# 24V_Buck.net
KiCad netlist of a schematic drawn in Altium Designer
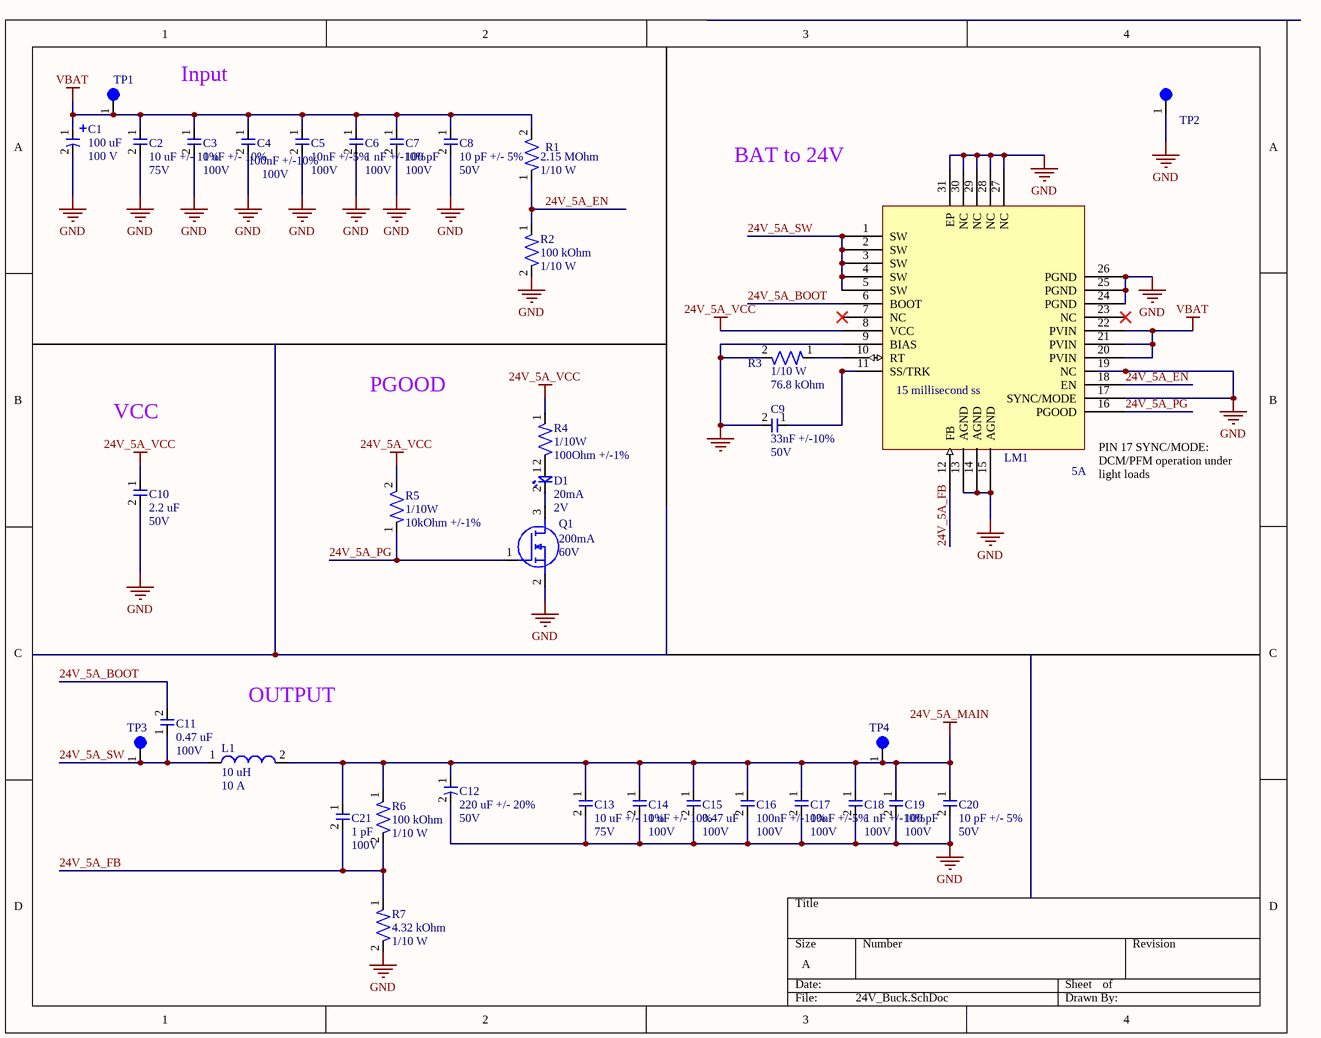
[diagram p0: 24V_Buck.SchDoc]

(export (version "E")
  (design (tool "Eeschema 10.0.6"))
  (components
    (comp (ref "C1")
      (value "100SEV100M12.5X16")
      (footprint "ELEC-100U-0001")
      (description "100 µF 100 V Aluminum Electrolytic Capacitors Radial, Can - SMD 2000 Hrs @ 85°C")
      (fields
        (field (name "MANUFACTURER") "Rubycon")
        (field (name "TOLERANCE") "+/- 20%")
        (field (name "CAPACITANCE") "100 uF")
        (field (name "VOLTAGE") "100 V")
      )
      (libsource (lib "MasterLib") (part "ELEC-100U-0001"))
    )
    (comp (ref "C2")
      (value "C3225X7R1N106K250AC")
      (footprint "CAP-1210")
      (description "10 µF ±10% 75V Ceramic Capacitor X7R 1210 (3225 Metric)")
      (fields (field (name "CAPACITANCE") "10 uF +/- 10%") (field (name "VOLTAGE RATING") "75V"))
      (libsource (lib "MasterLib") (part "CAP-10U-0004"))
    )
    (comp (ref "C3")
      (value "CL31B105KCHNNNE")
      (footprint "CAP-1206 - duplicate")
      (description "1 µF ±10% 100V Ceramic Capacitor X7R 1206 (3216 Metric)")
      (fields (field (name "CAPACITANCE") "1 uF +/- 10%") (field (name "VOLTAGE") "100V"))
      (libsource (lib "MasterLib") (part "CAP-1U-0001"))
    )
    (comp (ref "C4")
      (value "CC0603KRX7R0BB104")
      (footprint "CAP-0603")
      (description "CAP CER 0.1UF 100V X7R 0603")
      (fields
        (field (name "MANUFACTURER") "YAGEO")
        (field (name "CAPACITANCE") "100nF +/-10%")
        (field (name "VOLTAGE RATING") "100V")
      )
      (libsource (lib "MasterLib") (part "CAP-100N-0001"))
    )
    (comp (ref "C5")
      (value "C1608C0G2A103J080AC")
      (footprint "CAP-0603")
      (description "CAP CER 10000PF 100V C0G 0603")
      (fields
        (field (name "MANUFACTURER") "TDK Corporation")
        (field (name "CAPACITANCE") "10nF +/-5%")
        (field (name "VOLTAGE RATING") "100V")
      )
      (libsource (lib "MasterLib") (part "CAP-10N-0002"))
    )
    (comp (ref "C6")
      (value "C0603Y102K1RAC7867")
      (footprint "CAP-0603")
      (description "1000 pF ±10% 100V Ceramic Capacitor X7R 0603 (1608 Metric)")
      (fields (field (name "CAPACITANCE") "1 nF +/-10%") (field (name "VOLTAGE") "100V"))
      (libsource (lib "MasterLib") (part "CAP-1N-0001"))
    )
    (comp (ref "C7")
      (value "0603N101J101CT")
      (footprint "CAP-0603")
      (description "100 pF ±5% 100V Ceramic Capacitor C0G, NP0 0603 (1608 Metric)")
      (fields
        (field (name "TOLERANCE") "+/-5%")
        (field (name "CAPACITANCE") "100 pF")
        (field (name "VOLTAGE") "100V")
      )
      (libsource (lib "MasterLib") (part "CAP-100P-0002"))
    )
    (comp (ref "C8")
      (value "0603N100J500CT")
      (footprint "CAP-0603")
      (description "10 pF ±5% 50V Ceramic Capacitor C0G, NP0 0603 (1608 Metric)")
      (fields
        (field (name "MANUFACTURER") "Walshin Technology Corporation")
        (field (name "CAPACITANCE") "10 pF +/- 5%")
        (field (name "VOLTAGE RATING") "50V")
      )
      (libsource (lib "MasterLib") (part "CAP-10P-0001"))
    )
    (comp (ref "C9")
      (value "CC0603KRX7R9BB333")
      (footprint "CAP-0603")
      (description "0.033 µF ±10% 50V Ceramic Capacitor X7R 0603 (1608 Metric)")
      (fields
        (field (name "MANUFACTURER") "YAGEO")
        (field (name "CAPACITANCE") "33nF +/-10%")
        (field (name "VOLTAGE RATING") "50V")
      )
      (libsource (lib "MasterLib") (part "CAP-33N-0001"))
    )
    (comp (ref "C10")
      (value "UMK107BBJ225KA-T")
      (footprint "CAP-0603")
      (description "2.2 µF ±10% 50V Ceramic Capacitor X5R 0603 (1608 Metric)")
      (fields (field (name "CAPACITANCE") "2.2 uF") (field (name "OLTAGE") "50V"))
      (libsource (lib "MasterLib") (part "CAP-2.2U-0001"))
    )
    (comp (ref "C11")
      (value "KAM21KR72A474KL")
      (footprint "CAP-0805")
      (description "0.47 µF ±10% 100V Ceramic Capacitor X7R 0805 (2012 Metric)")
      (fields
        (field (name "TOLERANCE") "+/- 10%")
        (field (name "CAPACITANCE") "0.47 uF")
        (field (name "VOLTAGE") "100V")
      )
      (libsource (lib "MasterLib") (part "CAP-0.47U-0001"))
    )
    (comp (ref "C12")
      (value "50TZV220M10X10.5")
      (footprint "ELEC-220U-0003")
      (description "220 µF 50 V Aluminum Electrolytic Capacitors Radial, Can - SMD 2000 Hrs @ 105°C")
      (fields (field (name "CAPACITANCE") "220 uF +/- 20%") (field (name "VOLTAGE RATING") "50V"))
      (libsource (lib "MasterLib") (part "ELEC-220U-0003"))
    )
    (comp (ref "C13")
      (value "C3225X7R1N106K250AC")
      (footprint "CAP-1210")
      (description "10 µF ±10% 75V Ceramic Capacitor X7R 1210 (3225 Metric)")
      (fields (field (name "CAPACITANCE") "10 uF +/- 10%") (field (name "VOLTAGE RATING") "75V"))
      (libsource (lib "MasterLib") (part "CAP-10U-0004"))
    )
    (comp (ref "C14")
      (value "CL31B105KCHNNNE")
      (footprint "CAP-1206 - duplicate")
      (description "1 µF ±10% 100V Ceramic Capacitor X7R 1206 (3216 Metric)")
      (fields (field (name "CAPACITANCE") "1 uF +/- 10%") (field (name "VOLTAGE") "100V"))
      (libsource (lib "MasterLib") (part "CAP-1U-0001"))
    )
    (comp (ref "C15")
      (value "KAM21KR72A474KL")
      (footprint "CAP-0805")
      (description "0.47 µF ±10% 100V Ceramic Capacitor X7R 0805 (2012 Metric)")
      (fields
        (field (name "TOLERANCE") "+/- 10%")
        (field (name "CAPACITANCE") "0.47 uF")
        (field (name "VOLTAGE") "100V")
      )
      (libsource (lib "MasterLib") (part "CAP-0.47U-0001"))
    )
    (comp (ref "C16")
      (value "CC0603KRX7R0BB104")
      (footprint "CAP-0603")
      (description "CAP CER 0.1UF 100V X7R 0603")
      (fields
        (field (name "MANUFACTURER") "YAGEO")
        (field (name "CAPACITANCE") "100nF +/-10%")
        (field (name "VOLTAGE RATING") "100V")
      )
      (libsource (lib "MasterLib") (part "CAP-100N-0001"))
    )
    (comp (ref "C17")
      (value "C1608C0G2A103J080AC")
      (footprint "CAP-0603")
      (description "CAP CER 10000PF 100V C0G 0603")
      (fields
        (field (name "MANUFACTURER") "TDK Corporation")
        (field (name "CAPACITANCE") "10nF +/-5%")
        (field (name "VOLTAGE RATING") "100V")
      )
      (libsource (lib "MasterLib") (part "CAP-10N-0002"))
    )
    (comp (ref "C18")
      (value "C0603Y102K1RAC7867")
      (footprint "CAP-0603")
      (description "1000 pF ±10% 100V Ceramic Capacitor X7R 0603 (1608 Metric)")
      (fields (field (name "CAPACITANCE") "1 nF +/-10%") (field (name "VOLTAGE") "100V"))
      (libsource (lib "MasterLib") (part "CAP-1N-0001"))
    )
    (comp (ref "C19")
      (value "0603N101J101CT")
      (footprint "CAP-0603")
      (description "100 pF ±5% 100V Ceramic Capacitor C0G, NP0 0603 (1608 Metric)")
      (fields
        (field (name "TOLERANCE") "+/-5%")
        (field (name "CAPACITANCE") "100 pF")
        (field (name "VOLTAGE") "100V")
      )
      (libsource (lib "MasterLib") (part "CAP-100P-0002"))
    )
    (comp (ref "C20")
      (value "0603N100J500CT")
      (footprint "CAP-0603")
      (description "10 pF ±5% 50V Ceramic Capacitor C0G, NP0 0603 (1608 Metric)")
      (fields
        (field (name "MANUFACTURER") "Walshin Technology Corporation")
        (field (name "CAPACITANCE") "10 pF +/- 5%")
        (field (name "VOLTAGE RATING") "50V")
      )
      (libsource (lib "MasterLib") (part "CAP-10P-0001"))
    )
    (comp (ref "C21")
      (value "885012006087")
      (footprint "CAP-0603")
      (description "1 pF ±0.25pF 100V Ceramic Capacitor C0G, NP0 0603 (1608 Metric)")
      (fields
        (field (name "TOLERANCE") "+/- 0.25 pF")
        (field (name "CAPACITANCE") "1 pF")
        (field (name "VOLTAGE") "100V")
      )
      (libsource (lib "MasterLib") (part "CAP-1P-0001"))
    )
    (comp (ref "D1")
      (value "150060AS75000")
      (footprint "LED-0603")
      (description "CAP CER 0.1UF 100V X7R 0603")
      (fields
        (field (name "MANUFACTURER") "Wurth Electronik")
        (field (name "CURRENT RATING") "20mA")
        (field (name "VF") "2V")
      )
      (libsource (lib "MasterLib") (part "LED_Amber_0001"))
    )
    (comp (ref "L1")
      (value "SRP1270-100M")
      (footprint "PWRIND-10U-0002")
      (description "10 µH Shielded Drum Core, Wirewound Inductor 10 A 16.8mOhm Max Nonstandard")
      (fields
        (field (name "TOLERANCE") "+/- 20%")
        (field (name "INDUCTANCE") "10 uH")
        (field (name "DCI") "10 A")
      )
      (libsource (lib "MasterLib") (part "PWRIND-10U-0002"))
    )
    (comp (ref "LM1")
      (value "LM76005RNPR")
      (footprint "IC-30-WQFN(6x4)")
      (description "Buck Switching Regulator IC Positive Adjustable 1V 1 Output 5A 30-WFQFN Exposed Pad")
      (fields (field (name "MANUFACTURER") "Texas Instruments") (field (name "CURRENT") "5A"))
      (libsource (lib "MasterLib") (part "IC-BUCK-0006"))
    )
    (comp (ref "Q1")
      (value "T2N7002AK,LM")
      (footprint "NMOS-SOT23-3")
      (description "MOSFET N-CH 60V 200MA SOT23")
      (fields
        (field (name "MANUFACTURER") "Toshiba")
        (field (name "ID-CONTINUOUS") "200mA")
        (field (name "VDS-MAX") "60V")
      )
      (libsource (lib "MasterLib") (part "NMOS-200MA-0001"))
    )
    (comp (ref "R1")
      (value "RC0603FR-072M15L")
      (footprint "RES-0603")
      (description "2.15 MOhms ±1% 0.1W, 1/10W Chip Resistor 0603 (1608 Metric) Moisture Resistant Thick Film")
      (fields
        (field (name "TOLERANCE") "+/-1%")
        (field (name "RESISTANCE") "2.15 MOhm")
        (field (name "POWER") "1/10 W")
      )
      (libsource (lib "MasterLib") (part "RES-2.15M-0001"))
    )
    (comp (ref "R2")
      (value "RC0603FR-07100KL")
      (footprint "RES-0603")
      (description "100 kOhms ±1% 0.1W, 1/10W Chip Resistor 0603 (1608 Metric) Moisture Resistant Thick Film")
      (fields
        (field (name "TOLERANCE") "+/- 1%")
        (field (name "RESISTANCE") "100 kOhm")
        (field (name "POWER") "1/10 W")
      )
      (libsource (lib "MasterLib") (part "RES-100K-0003"))
    )
    (comp (ref "R3")
      (value "RC0603FR-0776K8L")
      (footprint "RES-0603")
      (description "76.8 kOhms ±1% 0.1W, 1/10W Chip Resistor 0603 (1608 Metric) Moisture Resistant Thick Film")
      (fields
        (field (name "MANUFACTURER") "Yageo")
        (field (name "TOLERANCE") "+/- 1%")
        (field (name "POWER") "1/10 W")
        (field (name "RESISTANCE") "76.8 kOhm")
      )
      (libsource (lib "MasterLib") (part "RES-76.8K-0001"))
    )
    (comp (ref "R4")
      (value "AC0603FR-10100RL")
      (footprint "RES-0603")
      (description "100 Ohms ±1% 0.1W, 1/10W Chip Resistor 0603 (1608 Metric) Automotive AEC-Q200 Thick Film")
      (fields
        (field (name "MANUFACTURER") "YAGEO")
        (field (name "POWER RATING") "1/10W")
        (field (name "RESISTANCE") "100Ohm +/-1%")
      )
      (libsource (lib "MasterLib") (part "RES-100-0002"))
    )
    (comp (ref "R5")
      (value "RC0603FR-0710KP")
      (footprint "RES-0603")
      (description "RES SMD 10K OHM 1% 1/10W 0603")
      (fields
        (field (name "MANUFACTURER") "YAGEO")
        (field (name "POWER RATING") "1/10W")
        (field (name "RESISTANCE") "10kOhm +/-1%")
      )
      (libsource (lib "MasterLib") (part "RES-10K-0002"))
    )
    (comp (ref "R6")
      (value "RC0603FR-07100KL")
      (footprint "RES-0603")
      (description "100 kOhms ±1% 0.1W, 1/10W Chip Resistor 0603 (1608 Metric) Moisture Resistant Thick Film")
      (fields
        (field (name "TOLERANCE") "+/- 1%")
        (field (name "RESISTANCE") "100 kOhm")
        (field (name "POWER") "1/10 W")
      )
      (libsource (lib "MasterLib") (part "RES-100K-0003"))
    )
    (comp (ref "R7")
      (value "RC0603FR-074K32L")
      (footprint "RES-0603")
      (description "4.32 kOhms ±1% 0.1W, 1/10W Chip Resistor 0603 (1608 Metric) Moisture Resistant Thick Film")
      (fields
        (field (name "TOLERANCE") "+/-1%")
        (field (name "RESISTANCE") "4.32 kOhm")
        (field (name "POWER") "1/10 W")
      )
      (libsource (lib "MasterLib") (part "RES-4.32K-0001"))
    )
    (comp (ref "TP1")
      (value "5003")
      (footprint "TEST-POINT-0001")
      (description "Oranange PC Test Point, Miniature Phoisphor Bronze Silver Plating Through Hole Mounting Type")
      (libsource (lib "MasterLib") (part "TEST-POINT-0001"))
    )
    (comp (ref "TP2")
      (value "5003")
      (footprint "TEST-POINT-0001")
      (description "Oranange PC Test Point, Miniature Phoisphor Bronze Silver Plating Through Hole Mounting Type")
      (libsource (lib "MasterLib") (part "TEST-POINT-0001"))
    )
    (comp (ref "TP3")
      (value "5003")
      (footprint "TEST-POINT-0001")
      (description "Oranange PC Test Point, Miniature Phoisphor Bronze Silver Plating Through Hole Mounting Type")
      (libsource (lib "MasterLib") (part "TEST-POINT-0001"))
    )
    (comp (ref "TP4")
      (value "5003")
      (footprint "TEST-POINT-0001")
      (description "Oranange PC Test Point, Miniature Phoisphor Bronze Silver Plating Through Hole Mounting Type")
      (libsource (lib "MasterLib") (part "TEST-POINT-0001"))
    )
  )
  (nets
    (net (code "1") (name "/24V_5A_BOOT") (class "Default")
      (node (ref "C11") (pin "2") (pinfunction "2_2") (pintype "passive"))
      (node (ref "LM1") (pin "6") (pinfunction "BOOT_6") (pintype "power_in"))
    )
    (net (code "2") (name "/24V_5A_EN") (class "Default")
      (node (ref "LM1") (pin "18") (pinfunction "EN_18") (pintype "power_in"))
      (node (ref "R1") (pin "1") (pinfunction "1_1") (pintype "passive"))
      (node (ref "R2") (pin "1") (pinfunction "1_1") (pintype "passive"))
    )
    (net (code "3") (name "/24V_5A_FB") (class "Default")
      (node (ref "C21") (pin "2") (pinfunction "2_2") (pintype "passive"))
      (node (ref "LM1") (pin "12") (pinfunction "FB_12") (pintype "input"))
      (node (ref "R6") (pin "2") (pinfunction "2_2") (pintype "passive"))
      (node (ref "R7") (pin "1") (pinfunction "1_1") (pintype "passive"))
    )
    (net (code "4") (name "/24V_5A_PG") (class "Default")
      (node (ref "LM1") (pin "16") (pinfunction "PGOOD_16") (pintype "power_in"))
      (node (ref "Q1") (pin "1") (pinfunction "G_1") (pintype "passive"))
      (node (ref "R5") (pin "1") (pinfunction "1_1") (pintype "passive"))
    )
    (net (code "5") (name "/24V_5A_SW") (class "Default")
      (node (ref "C11") (pin "1") (pinfunction "1_1") (pintype "passive"))
      (node (ref "L1") (pin "1") (pinfunction "1_1") (pintype "passive"))
      (node (ref "LM1") (pin "1") (pinfunction "SW_1") (pintype "power_in"))
      (node (ref "LM1") (pin "2") (pinfunction "SW_2") (pintype "power_in"))
      (node (ref "LM1") (pin "3") (pinfunction "SW_3") (pintype "power_in"))
      (node (ref "LM1") (pin "4") (pinfunction "SW_4") (pintype "power_in"))
      (node (ref "LM1") (pin "5") (pinfunction "SW_5") (pintype "power_in"))
      (node (ref "TP3") (pin "1") (pinfunction "0_1") (pintype "passive"))
    )
    (net (code "6") (name "24V_5A_MAIN") (class "Default")
      (node (ref "C12") (pin "1") (pinfunction "1_1") (pintype "passive"))
      (node (ref "C13") (pin "1") (pinfunction "1_1") (pintype "passive"))
      (node (ref "C14") (pin "1") (pinfunction "1_1") (pintype "passive"))
      (node (ref "C15") (pin "1") (pinfunction "1_1") (pintype "passive"))
      (node (ref "C16") (pin "1") (pinfunction "1_1") (pintype "passive"))
      (node (ref "C17") (pin "1") (pinfunction "1_1") (pintype "passive"))
      (node (ref "C18") (pin "1") (pinfunction "1_1") (pintype "passive"))
      (node (ref "C19") (pin "1") (pinfunction "1_1") (pintype "passive"))
      (node (ref "C20") (pin "1") (pinfunction "1_1") (pintype "passive"))
      (node (ref "C21") (pin "1") (pinfunction "1_1") (pintype "passive"))
      (node (ref "L1") (pin "2") (pinfunction "2_2") (pintype "passive"))
      (node (ref "R6") (pin "1") (pinfunction "1_1") (pintype "passive"))
      (node (ref "TP4") (pin "1") (pinfunction "0_1") (pintype "passive"))
    )
    (net (code "7") (name "24V_5A_VCC") (class "Default")
      (node (ref "C10") (pin "1") (pinfunction "1_1") (pintype "passive"))
      (node (ref "LM1") (pin "8") (pinfunction "VCC_8") (pintype "power_in"))
      (node (ref "R4") (pin "1") (pinfunction "1_1") (pintype "passive"))
      (node (ref "R5") (pin "2") (pinfunction "2_2") (pintype "passive"))
    )
    (net (code "8") (name "<NO NET>") (class "Default")
      (node (ref "C9") (pin "2") (pinfunction "2_2") (pintype "passive"))
      (node (ref "LM1") (pin "9") (pinfunction "BIAS_9") (pintype "power_in"))
      (node (ref "R3") (pin "2") (pinfunction "2_2") (pintype "passive"))
    )
    (net (code "9") (name "GND") (class "Default")
      (node (ref "C1") (pin "2") (pinfunction "2_2") (pintype "passive"))
      (node (ref "C10") (pin "2") (pinfunction "2_2") (pintype "passive"))
      (node (ref "C12") (pin "2") (pinfunction "2_2") (pintype "passive"))
      (node (ref "C13") (pin "2") (pinfunction "2_2") (pintype "passive"))
      (node (ref "C14") (pin "2") (pinfunction "2_2") (pintype "passive"))
      (node (ref "C15") (pin "2") (pinfunction "2_2") (pintype "passive"))
      (node (ref "C16") (pin "2") (pinfunction "2_2") (pintype "passive"))
      (node (ref "C17") (pin "2") (pinfunction "2_2") (pintype "passive"))
      (node (ref "C18") (pin "2") (pinfunction "2_2") (pintype "passive"))
      (node (ref "C19") (pin "2") (pinfunction "2_2") (pintype "passive"))
      (node (ref "C2") (pin "2") (pinfunction "2_2") (pintype "passive"))
      (node (ref "C20") (pin "2") (pinfunction "2_2") (pintype "passive"))
      (node (ref "C3") (pin "2") (pinfunction "2_2") (pintype "passive"))
      (node (ref "C4") (pin "2") (pinfunction "2_2") (pintype "passive"))
      (node (ref "C5") (pin "2") (pinfunction "2_2") (pintype "passive"))
      (node (ref "C6") (pin "2") (pinfunction "2_2") (pintype "passive"))
      (node (ref "C7") (pin "2") (pinfunction "2_2") (pintype "passive"))
      (node (ref "C8") (pin "2") (pinfunction "2_2") (pintype "passive"))
      (node (ref "LM1") (pin "13") (pinfunction "AGND_13") (pintype "power_in"))
      (node (ref "LM1") (pin "14") (pinfunction "AGND_14") (pintype "power_in"))
      (node (ref "LM1") (pin "15") (pinfunction "AGND_15") (pintype "power_in"))
      (node (ref "LM1") (pin "17") (pinfunction "SYNC/MODE_17") (pintype "power_in"))
      (node (ref "LM1") (pin "19") (pinfunction "NC_19") (pintype "power_in"))
      (node (ref "LM1") (pin "24") (pinfunction "PGND_24") (pintype "power_in"))
      (node (ref "LM1") (pin "25") (pinfunction "PGND_25") (pintype "power_in"))
      (node (ref "LM1") (pin "26") (pinfunction "PGND_26") (pintype "power_in"))
      (node (ref "LM1") (pin "27") (pinfunction "NC_27") (pintype "power_in"))
      (node (ref "LM1") (pin "28") (pinfunction "NC_28") (pintype "power_in"))
      (node (ref "LM1") (pin "29") (pinfunction "NC_29") (pintype "power_in"))
      (node (ref "LM1") (pin "30") (pinfunction "NC_30") (pintype "power_in"))
      (node (ref "LM1") (pin "31") (pinfunction "EP_31") (pintype "power_in"))
      (node (ref "Q1") (pin "2") (pinfunction "S_2") (pintype "passive"))
      (node (ref "R2") (pin "2") (pinfunction "2_2") (pintype "passive"))
      (node (ref "R7") (pin "2") (pinfunction "2_2") (pintype "passive"))
      (node (ref "TP2") (pin "1") (pinfunction "0_1") (pintype "passive"))
    )
    (net (code "10") (name "Net-(D1-Pad1)") (class "Default")
      (node (ref "D1") (pin "1") (pinfunction "1_1") (pintype "passive"))
      (node (ref "R4") (pin "2") (pinfunction "2_2") (pintype "passive"))
    )
    (net (code "11") (name "Net-(LM1-RT)") (class "Default")
      (node (ref "LM1") (pin "10") (pinfunction "RT_10") (pintype "bidirectional"))
      (node (ref "R3") (pin "1") (pinfunction "1_1") (pintype "passive"))
    )
    (net (code "12") (name "Net-(LM1-SS{slash}TRK)") (class "Default")
      (node (ref "C9") (pin "1") (pinfunction "1_1") (pintype "passive"))
      (node (ref "LM1") (pin "11") (pinfunction "SS/TRK_11") (pintype "passive"))
    )
    (net (code "13") (name "Net-(Q1-D)") (class "Default")
      (node (ref "D1") (pin "2") (pinfunction "2_2") (pintype "passive"))
      (node (ref "Q1") (pin "3") (pinfunction "D_3") (pintype "passive"))
    )
    (net (code "14") (name "VBAT") (class "Default")
      (node (ref "C1") (pin "1") (pinfunction "1_1") (pintype "passive"))
      (node (ref "C2") (pin "1") (pinfunction "1_1") (pintype "passive"))
      (node (ref "C3") (pin "1") (pinfunction "1_1") (pintype "passive"))
      (node (ref "C4") (pin "1") (pinfunction "1_1") (pintype "passive"))
      (node (ref "C5") (pin "1") (pinfunction "1_1") (pintype "passive"))
      (node (ref "C6") (pin "1") (pinfunction "1_1") (pintype "passive"))
      (node (ref "C7") (pin "1") (pinfunction "1_1") (pintype "passive"))
      (node (ref "C8") (pin "1") (pinfunction "1_1") (pintype "passive"))
      (node (ref "LM1") (pin "20") (pinfunction "PVIN_20") (pintype "power_in"))
      (node (ref "LM1") (pin "21") (pinfunction "PVIN_21") (pintype "power_in"))
      (node (ref "LM1") (pin "22") (pinfunction "PVIN_22") (pintype "power_in"))
      (node (ref "R1") (pin "2") (pinfunction "2_2") (pintype "passive"))
      (node (ref "TP1") (pin "1") (pinfunction "0_1") (pintype "passive"))
    )
    (net (code "15") (name "unconnected-(LM1-NC-Pad7)") (class "Default")
      (node (ref "LM1") (pin "7") (pinfunction "NC_7") (pintype "power_in+no_connect"))
    )
    (net (code "16") (name "unconnected-(LM1-NC-Pad23)") (class "Default")
      (node (ref "LM1") (pin "23") (pinfunction "NC_23") (pintype "tri_state+no_connect"))
    )
  )
)
